# 8_imu_debug_conn.net
KiCad netlist of a schematic drawn in Altium Designer
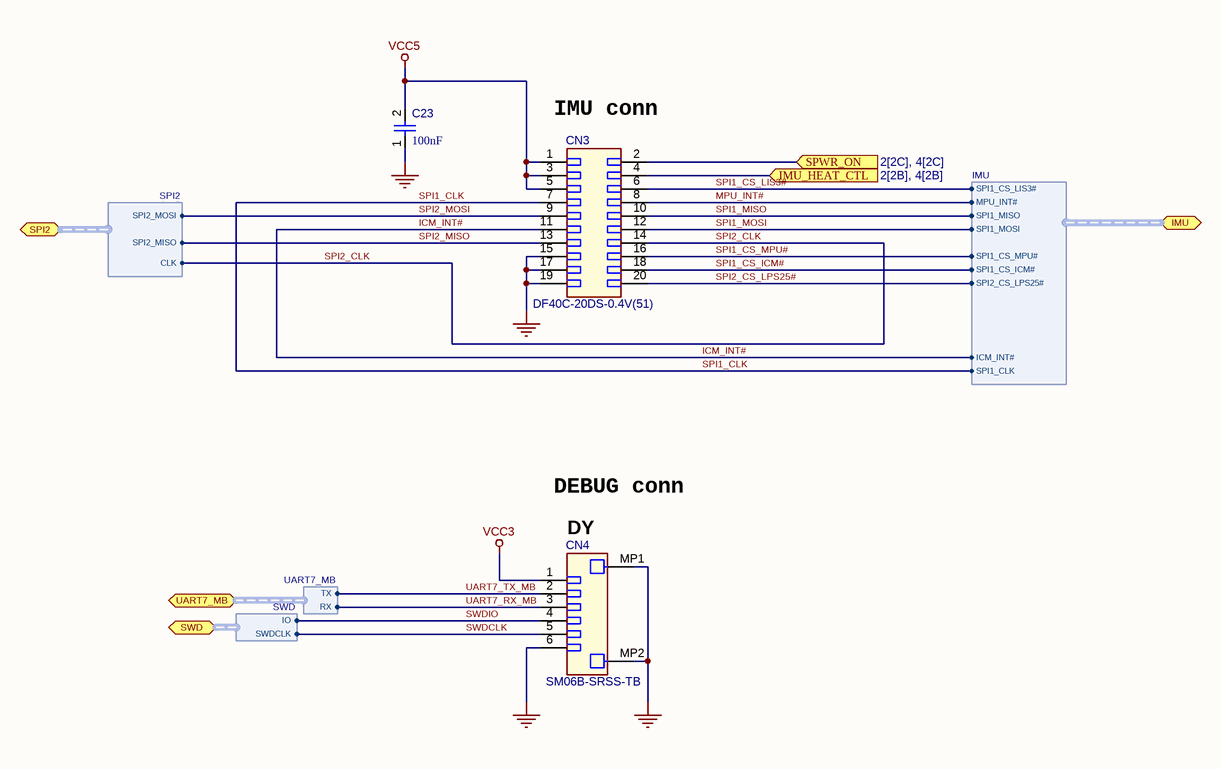
[diagram p0: 8_imu&debug_conn.SchDoc]

(export (version "E")
  (design (tool "Eeschema 10.0.6"))
  (components
    (comp (ref "C23")
      (value "100nF")
      (footprint "CAPC0402(1005)60_L")
      (description "Chip Capacitor, 100nF +/-20%, 10V, 0402, Thickness 0.6 mm")
      (fields (field (name "TOLERANCE") "20%") (field (name "Comment") "Capacitor 100nF +/-20% 10V 0402"))
      (libsource (lib "<Company> Server") (part "CAP-NP-2"))
    )
    (comp (ref "CN3")
      (value "DF40C-20DS-0.4V(51)")
      (footprint "HIRO-DF40C-20DS-0.4V(51)_V")
      (description "Receptacle Connector, 30 V, 0.3 A, -35 to 85 degC, RoHS, Tape and Reel")
      (libsource (lib "<Company> Server") (part "CMP-00114-7"))
    )
    (comp (ref "CN4")
      (value "SM06B-SRSS-TB")
      (footprint "JST-SM06B-SRSS-TB_V")
      (description "Male Header, Pitch 1 mm, 1 x 6 Position, Height 2.95 mm, -25 to 85 degC, RoHS, Tape and Reel")
      (libsource (lib "<Company> Server") (part "CMP-00143-5"))
    )
  )
  (nets
    (net (code "5") (name "/ICM_INT#") (class "Default")
      (node (ref "CN3") (pin "11") (pinfunction "11_11") (pintype "passive"))
    )
    (net (code "6") (name "/IMU_HEAT_CTL") (class "Default")
      (node (ref "CN3") (pin "4") (pinfunction "4_4") (pintype "passive"))
    )
    (net (code "7") (name "/MPU_INT#") (class "Default")
      (node (ref "CN3") (pin "8") (pinfunction "8_8") (pintype "passive"))
    )
    (net (code "8") (name "/SPI1_CLK") (class "Default")
      (node (ref "CN3") (pin "7") (pinfunction "7_7") (pintype "passive"))
    )
    (net (code "9") (name "/SPI1_CS_ICM#") (class "Default")
      (node (ref "CN3") (pin "18") (pinfunction "18_18") (pintype "passive"))
    )
    (net (code "10") (name "/SPI1_CS_LIS3#") (class "Default")
      (node (ref "CN3") (pin "6") (pinfunction "6_6") (pintype "passive"))
    )
    (net (code "11") (name "/SPI1_CS_MPU#") (class "Default")
      (node (ref "CN3") (pin "16") (pinfunction "16_16") (pintype "passive"))
    )
    (net (code "12") (name "/SPI1_MISO") (class "Default")
      (node (ref "CN3") (pin "10") (pinfunction "10_10") (pintype "passive"))
    )
    (net (code "13") (name "/SPI1_MOSI") (class "Default")
      (node (ref "CN3") (pin "12") (pinfunction "12_12") (pintype "passive"))
    )
    (net (code "14") (name "/SPI2_CLK") (class "Default")
      (node (ref "CN3") (pin "14") (pinfunction "14_14") (pintype "passive"))
    )
    (net (code "15") (name "/SPI2_CS_LPS25#") (class "Default")
      (node (ref "CN3") (pin "20") (pinfunction "20_20") (pintype "passive"))
    )
    (net (code "16") (name "/SPI2_MISO") (class "Default")
      (node (ref "CN3") (pin "13") (pinfunction "13_13") (pintype "passive"))
    )
    (net (code "17") (name "/SPI2_MOSI") (class "Default")
      (node (ref "CN3") (pin "9") (pinfunction "9_9") (pintype "passive"))
    )
    (net (code "18") (name "/SPWR_ON") (class "Default")
      (node (ref "CN3") (pin "2") (pinfunction "2_2") (pintype "passive"))
    )
    (net (code "19") (name "/SWDCLK") (class "Default")
      (node (ref "CN4") (pin "5") (pinfunction "5_5") (pintype "passive"))
    )
    (net (code "20") (name "/SWDIO") (class "Default")
      (node (ref "CN4") (pin "4") (pinfunction "4_4") (pintype "passive"))
    )
    (net (code "21") (name "/UART7_RX_MB") (class "Default")
      (node (ref "CN4") (pin "3") (pinfunction "3_3") (pintype "passive"))
    )
    (net (code "22") (name "/UART7_TX_MB") (class "Default")
      (node (ref "CN4") (pin "2") (pinfunction "2_2") (pintype "passive"))
    )
    (net (code "27") (name "GND") (class "Default")
      (node (ref "C23") (pin "1") (pinfunction "1_1") (pintype "passive"))
      (node (ref "CN3") (pin "15") (pinfunction "15_15") (pintype "passive"))
      (node (ref "CN3") (pin "17") (pinfunction "17_17") (pintype "passive"))
      (node (ref "CN3") (pin "19") (pinfunction "19_19") (pintype "passive"))
      (node (ref "CN4") (pin "6") (pinfunction "6_6") (pintype "passive"))
      (node (ref "CN4") (pin "MP1") (pinfunction "MP1_MP1") (pintype "passive"))
      (node (ref "CN4") (pin "MP2") (pinfunction "MP2_MP2") (pintype "passive"))
    )
    (net (code "28") (name "VCC3") (class "Default")
      (node (ref "CN4") (pin "1") (pinfunction "1_1") (pintype "passive"))
    )
    (net (code "29") (name "VCC5") (class "Default")
      (node (ref "C23") (pin "2") (pinfunction "2_2") (pintype "passive"))
      (node (ref "CN3") (pin "1") (pinfunction "1_1") (pintype "passive"))
      (node (ref "CN3") (pin "3") (pinfunction "3_3") (pintype "passive"))
      (node (ref "CN3") (pin "5") (pinfunction "5_5") (pintype "passive"))
    )
  )
)
